# optocoupler-shield.net
KiCad netlist of a schematic drawn in EAGLE
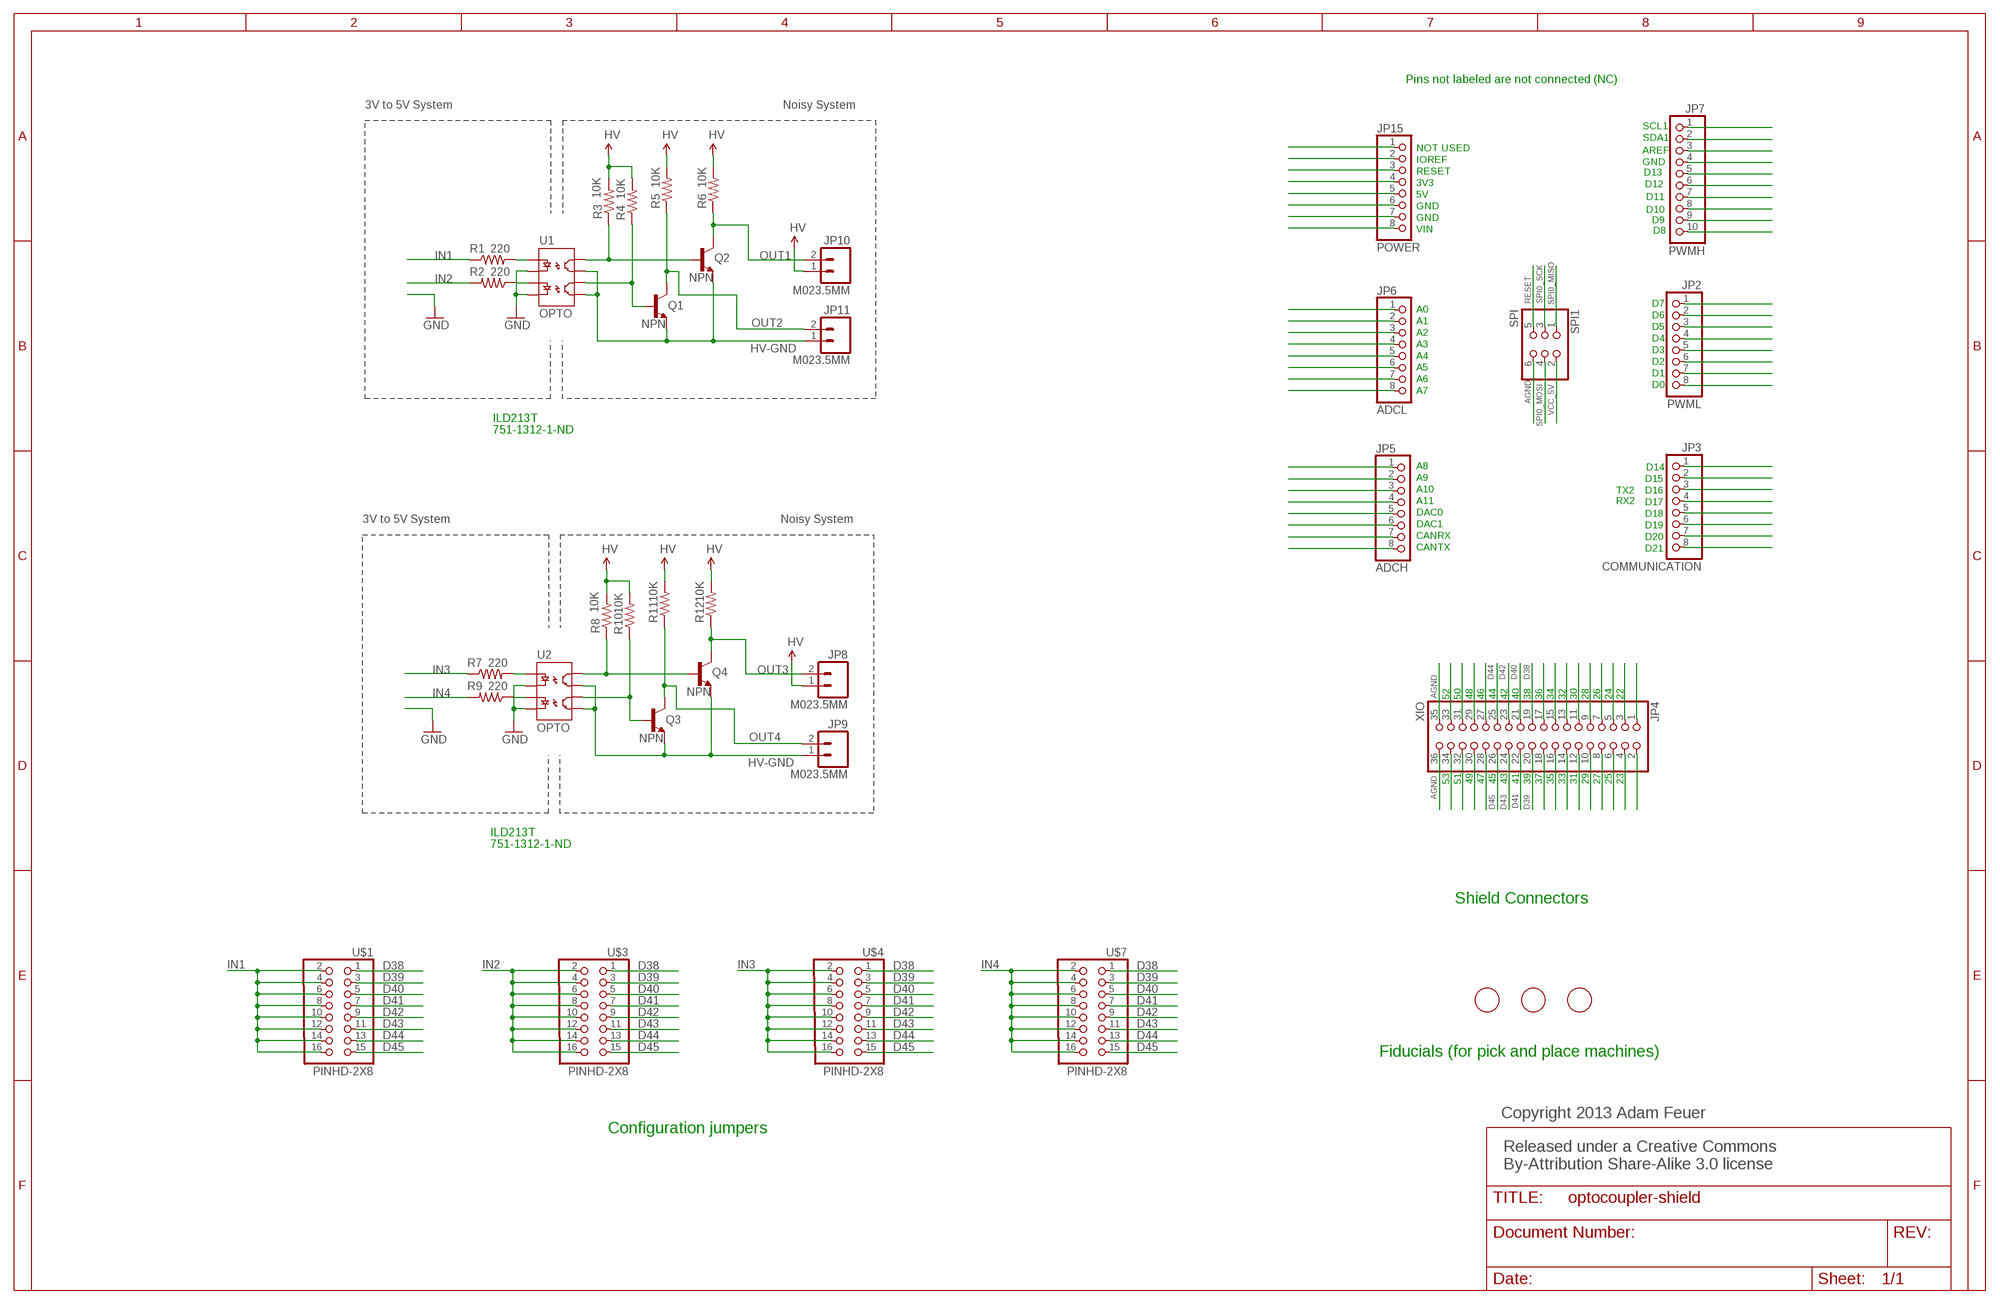
[diagram p0: schematic, sheet 1]

(export (version "E")
  (design (tool "Eeschema 10.0.6"))
  (components
    (comp (ref "JP2")
      (value "PWML")
      (footprint "eagle-import:1X08")
      (libsource (lib "eagle-import") (part "PINHD-1X8"))
    )
    (comp (ref "JP3")
      (value "COMMUNICATION")
      (footprint "eagle-import:1X08")
      (libsource (lib "eagle-import") (part "PINHD-1X8"))
    )
    (comp (ref "JP4")
      (value "XIO")
      (footprint "eagle-import:2X18")
      (libsource (lib "eagle-import") (part "PINHD-2X18"))
    )
    (comp (ref "JP5")
      (value "ADCH")
      (footprint "eagle-import:1X08")
      (libsource (lib "eagle-import") (part "PINHD-1X8"))
    )
    (comp (ref "JP6")
      (value "ADCL")
      (footprint "eagle-import:1X08")
      (libsource (lib "eagle-import") (part "PINHD-1X8"))
    )
    (comp (ref "JP7")
      (value "PWMH")
      (footprint "eagle-import:1X10")
      (libsource (lib "eagle-import") (part "PINHD-1X10"))
    )
    (comp (ref "JP8")
      (value "M023.5MM")
      (footprint "eagle-import:SCREWTERMINAL-3.5MM-2")
      (libsource (lib "eagle-import") (part "M023.5MM"))
    )
    (comp (ref "JP9")
      (value "M023.5MM")
      (footprint "eagle-import:SCREWTERMINAL-3.5MM-2")
      (libsource (lib "eagle-import") (part "M023.5MM"))
    )
    (comp (ref "JP10")
      (value "M023.5MM")
      (footprint "eagle-import:SCREWTERMINAL-3.5MM-2")
      (libsource (lib "eagle-import") (part "M023.5MM"))
    )
    (comp (ref "JP11")
      (value "M023.5MM")
      (footprint "eagle-import:SCREWTERMINAL-3.5MM-2")
      (libsource (lib "eagle-import") (part "M023.5MM"))
    )
    (comp (ref "JP15")
      (value "POWER")
      (footprint "eagle-import:1X08")
      (libsource (lib "eagle-import") (part "PINHD-1X8"))
    )
    (comp (ref "Q1")
      (value "NPN")
      (footprint "eagle-import:SOT23-3")
      (libsource (lib "eagle-import") (part "TRANSISTOR_NPNSOT23-3"))
    )
    (comp (ref "Q2")
      (value "NPN")
      (footprint "eagle-import:SOT23-3")
      (libsource (lib "eagle-import") (part "TRANSISTOR_NPNSOT23-3"))
    )
    (comp (ref "Q3")
      (value "NPN")
      (footprint "eagle-import:SOT23-3")
      (libsource (lib "eagle-import") (part "TRANSISTOR_NPNSOT23-3"))
    )
    (comp (ref "Q4")
      (value "NPN")
      (footprint "eagle-import:SOT23-3")
      (libsource (lib "eagle-import") (part "TRANSISTOR_NPNSOT23-3"))
    )
    (comp (ref "R1")
      (value "220")
      (footprint "eagle-import:C0402")
      (libsource (lib "eagle-import") (part "RESISTOR0402"))
    )
    (comp (ref "R2")
      (value "220")
      (footprint "eagle-import:C0402")
      (libsource (lib "eagle-import") (part "RESISTOR0402"))
    )
    (comp (ref "R3")
      (value "10K")
      (footprint "eagle-import:C0402")
      (libsource (lib "eagle-import") (part "RESISTOR0402"))
    )
    (comp (ref "R4")
      (value "10K")
      (footprint "eagle-import:C0402")
      (libsource (lib "eagle-import") (part "RESISTOR0402"))
    )
    (comp (ref "R5")
      (value "10K")
      (footprint "eagle-import:C0402")
      (libsource (lib "eagle-import") (part "RESISTOR0402"))
    )
    (comp (ref "R6")
      (value "10K")
      (footprint "eagle-import:C0402")
      (libsource (lib "eagle-import") (part "RESISTOR0402"))
    )
    (comp (ref "R7")
      (value "220")
      (footprint "eagle-import:C0402")
      (libsource (lib "eagle-import") (part "RESISTOR0402"))
    )
    (comp (ref "R8")
      (value "10K")
      (footprint "eagle-import:C0402")
      (libsource (lib "eagle-import") (part "RESISTOR0402"))
    )
    (comp (ref "R9")
      (value "220")
      (footprint "eagle-import:C0402")
      (libsource (lib "eagle-import") (part "RESISTOR0402"))
    )
    (comp (ref "R10")
      (value "10K")
      (footprint "eagle-import:C0402")
      (libsource (lib "eagle-import") (part "RESISTOR0402"))
    )
    (comp (ref "R11")
      (value "10K")
      (footprint "eagle-import:C0402")
      (libsource (lib "eagle-import") (part "RESISTOR0402"))
    )
    (comp (ref "R12")
      (value "10K")
      (footprint "eagle-import:C0402")
      (libsource (lib "eagle-import") (part "RESISTOR0402"))
    )
    (comp (ref "SPI1")
      (value "SPI")
      (footprint "eagle-import:2X03")
      (libsource (lib "eagle-import") (part "PINHD-2X3"))
    )
    (comp (ref "U$1")
      (value "PINHD-2X8")
      (footprint "eagle-import:2X08")
      (libsource (lib "eagle-import") (part "PINHD-2X8"))
    )
    (comp (ref "U$2")
      (value "FIDUCIAL")
      (footprint "eagle-import:FIDUCIAL_1MM")
      (libsource (lib "eagle-import") (part "FIDUCIAL"))
    )
    (comp (ref "U$3")
      (value "PINHD-2X8")
      (footprint "eagle-import:2X08")
      (libsource (lib "eagle-import") (part "PINHD-2X8"))
    )
    (comp (ref "U$4")
      (value "PINHD-2X8")
      (footprint "eagle-import:2X08")
      (libsource (lib "eagle-import") (part "PINHD-2X8"))
    )
    (comp (ref "U$5")
      (value "FIDUCIAL")
      (footprint "eagle-import:FIDUCIAL_1MM")
      (libsource (lib "eagle-import") (part "FIDUCIAL"))
    )
    (comp (ref "U$6")
      (value "FIDUCIAL")
      (footprint "eagle-import:FIDUCIAL_1MM")
      (libsource (lib "eagle-import") (part "FIDUCIAL"))
    )
    (comp (ref "U$7")
      (value "PINHD-2X8")
      (footprint "eagle-import:2X08")
      (libsource (lib "eagle-import") (part "PINHD-2X8"))
    )
    (comp (ref "U1")
      (value "OPTO")
      (footprint "eagle-import:SO08-2")
      (libsource (lib "eagle-import") (part "OPTOISOLATOR-2SOIC8"))
    )
    (comp (ref "U2")
      (value "OPTO")
      (footprint "eagle-import:SO08-2")
      (libsource (lib "eagle-import") (part "OPTOISOLATOR-2SOIC8"))
    )
  )
  (nets
    (net (code "1") (name "/AGND") (class "Default")
      (node (ref "JP4") (pin "35") (pinfunction "35_35") (pintype "passive"))
      (node (ref "JP4") (pin "36") (pinfunction "36_36") (pintype "passive"))
      (node (ref "SPI1") (pin "6") (pinfunction "6_6") (pintype "passive"))
    )
    (net (code "2") (name "/D38") (class "Default")
      (node (ref "JP4") (pin "19") (pinfunction "19_19") (pintype "passive"))
      (node (ref "U$1") (pin "1") (pinfunction "1_1") (pintype "passive"))
      (node (ref "U$3") (pin "1") (pinfunction "1_1") (pintype "passive"))
      (node (ref "U$4") (pin "1") (pinfunction "1_1") (pintype "passive"))
      (node (ref "U$7") (pin "1") (pinfunction "1_1") (pintype "passive"))
    )
    (net (code "3") (name "/D39") (class "Default")
      (node (ref "JP4") (pin "20") (pinfunction "20_20") (pintype "passive"))
      (node (ref "U$1") (pin "3") (pinfunction "3_3") (pintype "passive"))
      (node (ref "U$3") (pin "3") (pinfunction "3_3") (pintype "passive"))
      (node (ref "U$4") (pin "3") (pinfunction "3_3") (pintype "passive"))
      (node (ref "U$7") (pin "3") (pinfunction "3_3") (pintype "passive"))
    )
    (net (code "4") (name "/D40") (class "Default")
      (node (ref "JP4") (pin "21") (pinfunction "21_21") (pintype "passive"))
      (node (ref "U$1") (pin "5") (pinfunction "5_5") (pintype "passive"))
      (node (ref "U$3") (pin "5") (pinfunction "5_5") (pintype "passive"))
      (node (ref "U$4") (pin "5") (pinfunction "5_5") (pintype "passive"))
      (node (ref "U$7") (pin "5") (pinfunction "5_5") (pintype "passive"))
    )
    (net (code "5") (name "/D41") (class "Default")
      (node (ref "JP4") (pin "22") (pinfunction "22_22") (pintype "passive"))
      (node (ref "U$1") (pin "7") (pinfunction "7_7") (pintype "passive"))
      (node (ref "U$3") (pin "7") (pinfunction "7_7") (pintype "passive"))
      (node (ref "U$4") (pin "7") (pinfunction "7_7") (pintype "passive"))
      (node (ref "U$7") (pin "7") (pinfunction "7_7") (pintype "passive"))
    )
    (net (code "6") (name "/D42") (class "Default")
      (node (ref "JP4") (pin "23") (pinfunction "23_23") (pintype "passive"))
      (node (ref "U$1") (pin "9") (pinfunction "9_9") (pintype "passive"))
      (node (ref "U$3") (pin "9") (pinfunction "9_9") (pintype "passive"))
      (node (ref "U$4") (pin "9") (pinfunction "9_9") (pintype "passive"))
      (node (ref "U$7") (pin "9") (pinfunction "9_9") (pintype "passive"))
    )
    (net (code "7") (name "/D43") (class "Default")
      (node (ref "JP4") (pin "24") (pinfunction "24_24") (pintype "passive"))
      (node (ref "U$1") (pin "11") (pinfunction "11_11") (pintype "passive"))
      (node (ref "U$3") (pin "11") (pinfunction "11_11") (pintype "passive"))
      (node (ref "U$4") (pin "11") (pinfunction "11_11") (pintype "passive"))
      (node (ref "U$7") (pin "11") (pinfunction "11_11") (pintype "passive"))
    )
    (net (code "8") (name "/D44") (class "Default")
      (node (ref "JP4") (pin "25") (pinfunction "25_25") (pintype "passive"))
      (node (ref "U$1") (pin "13") (pinfunction "13_13") (pintype "passive"))
      (node (ref "U$3") (pin "13") (pinfunction "13_13") (pintype "passive"))
      (node (ref "U$4") (pin "13") (pinfunction "13_13") (pintype "passive"))
      (node (ref "U$7") (pin "13") (pinfunction "13_13") (pintype "passive"))
    )
    (net (code "9") (name "/D45") (class "Default")
      (node (ref "JP4") (pin "26") (pinfunction "26_26") (pintype "passive"))
      (node (ref "U$1") (pin "15") (pinfunction "15_15") (pintype "passive"))
      (node (ref "U$3") (pin "15") (pinfunction "15_15") (pintype "passive"))
      (node (ref "U$4") (pin "15") (pinfunction "15_15") (pintype "passive"))
      (node (ref "U$7") (pin "15") (pinfunction "15_15") (pintype "passive"))
    )
    (net (code "10") (name "/HV-GND") (class "Default")
      (node (ref "JP11") (pin "1") (pinfunction "1_1") (pintype "passive"))
      (node (ref "JP9") (pin "1") (pinfunction "1_1") (pintype "passive"))
      (node (ref "Q1") (pin "2") (pinfunction "E_2") (pintype "passive"))
      (node (ref "Q2") (pin "2") (pinfunction "E_2") (pintype "passive"))
      (node (ref "Q3") (pin "2") (pinfunction "E_2") (pintype "passive"))
      (node (ref "Q4") (pin "2") (pinfunction "E_2") (pintype "passive"))
      (node (ref "U1") (pin "5") (pinfunction "EM2_5") (pintype "bidirectional"))
      (node (ref "U1") (pin "7") (pinfunction "EM1_7") (pintype "bidirectional"))
      (node (ref "U2") (pin "5") (pinfunction "EM2_5") (pintype "bidirectional"))
      (node (ref "U2") (pin "7") (pinfunction "EM1_7") (pintype "bidirectional"))
    )
    (net (code "11") (name "/IN1") (class "Default")
      (node (ref "R1") (pin "1") (pinfunction "1_1") (pintype "passive"))
      (node (ref "U$1") (pin "10") (pinfunction "10_10") (pintype "passive"))
      (node (ref "U$1") (pin "12") (pinfunction "12_12") (pintype "passive"))
      (node (ref "U$1") (pin "14") (pinfunction "14_14") (pintype "passive"))
      (node (ref "U$1") (pin "16") (pinfunction "16_16") (pintype "passive"))
      (node (ref "U$1") (pin "2") (pinfunction "2_2") (pintype "passive"))
      (node (ref "U$1") (pin "4") (pinfunction "4_4") (pintype "passive"))
      (node (ref "U$1") (pin "6") (pinfunction "6_6") (pintype "passive"))
      (node (ref "U$1") (pin "8") (pinfunction "8_8") (pintype "passive"))
    )
    (net (code "12") (name "/IN2") (class "Default")
      (node (ref "R2") (pin "2") (pinfunction "2_2") (pintype "passive"))
      (node (ref "U$3") (pin "10") (pinfunction "10_10") (pintype "passive"))
      (node (ref "U$3") (pin "12") (pinfunction "12_12") (pintype "passive"))
      (node (ref "U$3") (pin "14") (pinfunction "14_14") (pintype "passive"))
      (node (ref "U$3") (pin "16") (pinfunction "16_16") (pintype "passive"))
      (node (ref "U$3") (pin "2") (pinfunction "2_2") (pintype "passive"))
      (node (ref "U$3") (pin "4") (pinfunction "4_4") (pintype "passive"))
      (node (ref "U$3") (pin "6") (pinfunction "6_6") (pintype "passive"))
      (node (ref "U$3") (pin "8") (pinfunction "8_8") (pintype "passive"))
    )
    (net (code "13") (name "/IN3") (class "Default")
      (node (ref "R7") (pin "1") (pinfunction "1_1") (pintype "passive"))
      (node (ref "U$4") (pin "10") (pinfunction "10_10") (pintype "passive"))
      (node (ref "U$4") (pin "12") (pinfunction "12_12") (pintype "passive"))
      (node (ref "U$4") (pin "14") (pinfunction "14_14") (pintype "passive"))
      (node (ref "U$4") (pin "16") (pinfunction "16_16") (pintype "passive"))
      (node (ref "U$4") (pin "2") (pinfunction "2_2") (pintype "passive"))
      (node (ref "U$4") (pin "4") (pinfunction "4_4") (pintype "passive"))
      (node (ref "U$4") (pin "6") (pinfunction "6_6") (pintype "passive"))
      (node (ref "U$4") (pin "8") (pinfunction "8_8") (pintype "passive"))
    )
    (net (code "14") (name "/IN4") (class "Default")
      (node (ref "R9") (pin "2") (pinfunction "2_2") (pintype "passive"))
      (node (ref "U$7") (pin "10") (pinfunction "10_10") (pintype "passive"))
      (node (ref "U$7") (pin "12") (pinfunction "12_12") (pintype "passive"))
      (node (ref "U$7") (pin "14") (pinfunction "14_14") (pintype "passive"))
      (node (ref "U$7") (pin "16") (pinfunction "16_16") (pintype "passive"))
      (node (ref "U$7") (pin "2") (pinfunction "2_2") (pintype "passive"))
      (node (ref "U$7") (pin "4") (pinfunction "4_4") (pintype "passive"))
      (node (ref "U$7") (pin "6") (pinfunction "6_6") (pintype "passive"))
      (node (ref "U$7") (pin "8") (pinfunction "8_8") (pintype "passive"))
    )
    (net (code "15") (name "/OUT1") (class "Default")
      (node (ref "JP10") (pin "2") (pinfunction "2_2") (pintype "passive"))
      (node (ref "Q2") (pin "3") (pinfunction "C_3") (pintype "passive"))
      (node (ref "R6") (pin "1") (pinfunction "1_1") (pintype "passive"))
    )
    (net (code "16") (name "/OUT2") (class "Default")
      (node (ref "JP11") (pin "2") (pinfunction "2_2") (pintype "passive"))
      (node (ref "Q1") (pin "3") (pinfunction "C_3") (pintype "passive"))
      (node (ref "R5") (pin "1") (pinfunction "1_1") (pintype "passive"))
    )
    (net (code "17") (name "/OUT3") (class "Default")
      (node (ref "JP8") (pin "2") (pinfunction "2_2") (pintype "passive"))
      (node (ref "Q4") (pin "3") (pinfunction "C_3") (pintype "passive"))
      (node (ref "R12") (pin "1") (pinfunction "1_1") (pintype "passive"))
    )
    (net (code "18") (name "/OUT4") (class "Default")
      (node (ref "JP9") (pin "2") (pinfunction "2_2") (pintype "passive"))
      (node (ref "Q3") (pin "3") (pinfunction "C_3") (pintype "passive"))
      (node (ref "R11") (pin "1") (pinfunction "1_1") (pintype "passive"))
    )
    (net (code "19") (name "/RESET") (class "Default")
      (node (ref "SPI1") (pin "5") (pinfunction "5_5") (pintype "passive"))
    )
    (net (code "20") (name "/SPI0_MISO") (class "Default")
      (node (ref "SPI1") (pin "1") (pinfunction "1_1") (pintype "passive"))
    )
    (net (code "21") (name "/SPI0_MOSI") (class "Default")
      (node (ref "SPI1") (pin "4") (pinfunction "4_4") (pintype "passive"))
    )
    (net (code "22") (name "/SPI0_SCK") (class "Default")
      (node (ref "SPI1") (pin "3") (pinfunction "3_3") (pintype "passive"))
    )
    (net (code "23") (name "/VCC_5V") (class "Default")
      (node (ref "SPI1") (pin "2") (pinfunction "2_2") (pintype "passive"))
    )
    (net (code "24") (name "GND") (class "Default")
      (node (ref "U1") (pin "2") (pinfunction "C1_2") (pintype "bidirectional"))
      (node (ref "U1") (pin "4") (pinfunction "C2_4") (pintype "bidirectional"))
      (node (ref "U2") (pin "2") (pinfunction "C1_2") (pintype "bidirectional"))
      (node (ref "U2") (pin "4") (pinfunction "C2_4") (pintype "bidirectional"))
    )
    (net (code "25") (name "HV") (class "Default")
      (node (ref "JP10") (pin "1") (pinfunction "1_1") (pintype "passive"))
      (node (ref "JP8") (pin "1") (pinfunction "1_1") (pintype "passive"))
      (node (ref "R10") (pin "2") (pinfunction "2_2") (pintype "passive"))
      (node (ref "R11") (pin "2") (pinfunction "2_2") (pintype "passive"))
      (node (ref "R12") (pin "2") (pinfunction "2_2") (pintype "passive"))
      (node (ref "R3") (pin "2") (pinfunction "2_2") (pintype "passive"))
      (node (ref "R4") (pin "2") (pinfunction "2_2") (pintype "passive"))
      (node (ref "R5") (pin "2") (pinfunction "2_2") (pintype "passive"))
      (node (ref "R6") (pin "2") (pinfunction "2_2") (pintype "passive"))
      (node (ref "R8") (pin "2") (pinfunction "2_2") (pintype "passive"))
    )
    (net (code "26") (name "Net-(Q1-B)") (class "Default")
      (node (ref "Q1") (pin "1") (pinfunction "B_1") (pintype "passive"))
      (node (ref "R4") (pin "1") (pinfunction "1_1") (pintype "passive"))
      (node (ref "U1") (pin "6") (pinfunction "CL2_6") (pintype "bidirectional"))
    )
    (net (code "27") (name "Net-(Q2-B)") (class "Default")
      (node (ref "Q2") (pin "1") (pinfunction "B_1") (pintype "passive"))
      (node (ref "R3") (pin "1") (pinfunction "1_1") (pintype "passive"))
      (node (ref "U1") (pin "8") (pinfunction "CL1_8") (pintype "bidirectional"))
    )
    (net (code "28") (name "Net-(Q3-B)") (class "Default")
      (node (ref "Q3") (pin "1") (pinfunction "B_1") (pintype "passive"))
      (node (ref "R10") (pin "1") (pinfunction "1_1") (pintype "passive"))
      (node (ref "U2") (pin "6") (pinfunction "CL2_6") (pintype "bidirectional"))
    )
    (net (code "29") (name "Net-(Q4-B)") (class "Default")
      (node (ref "Q4") (pin "1") (pinfunction "B_1") (pintype "passive"))
      (node (ref "R8") (pin "1") (pinfunction "1_1") (pintype "passive"))
      (node (ref "U2") (pin "8") (pinfunction "CL1_8") (pintype "bidirectional"))
    )
    (net (code "30") (name "Net-(U1-A1)") (class "Default")
      (node (ref "R1") (pin "2") (pinfunction "2_2") (pintype "passive"))
      (node (ref "U1") (pin "1") (pinfunction "A1_1") (pintype "bidirectional"))
    )
    (net (code "31") (name "Net-(U1-A2)") (class "Default")
      (node (ref "R2") (pin "1") (pinfunction "1_1") (pintype "passive"))
      (node (ref "U1") (pin "3") (pinfunction "A2_3") (pintype "bidirectional"))
    )
    (net (code "32") (name "Net-(U2-A1)") (class "Default")
      (node (ref "R7") (pin "2") (pinfunction "2_2") (pintype "passive"))
      (node (ref "U2") (pin "1") (pinfunction "A1_1") (pintype "bidirectional"))
    )
    (net (code "33") (name "Net-(U2-A2)") (class "Default")
      (node (ref "R9") (pin "1") (pinfunction "1_1") (pintype "passive"))
      (node (ref "U2") (pin "3") (pinfunction "A2_3") (pintype "bidirectional"))
    )
    (net (code "34") (name "unconnected-(JP2-Pad1)") (class "Default")
      (node (ref "JP2") (pin "1") (pinfunction "1_1") (pintype "passive"))
    )
    (net (code "35") (name "unconnected-(JP2-Pad2)") (class "Default")
      (node (ref "JP2") (pin "2") (pinfunction "2_2") (pintype "passive"))
    )
    (net (code "36") (name "unconnected-(JP2-Pad3)") (class "Default")
      (node (ref "JP2") (pin "3") (pinfunction "3_3") (pintype "passive"))
    )
    (net (code "37") (name "unconnected-(JP2-Pad4)") (class "Default")
      (node (ref "JP2") (pin "4") (pinfunction "4_4") (pintype "passive"))
    )
    (net (code "38") (name "unconnected-(JP2-Pad5)") (class "Default")
      (node (ref "JP2") (pin "5") (pinfunction "5_5") (pintype "passive"))
    )
    (net (code "39") (name "unconnected-(JP2-Pad6)") (class "Default")
      (node (ref "JP2") (pin "6") (pinfunction "6_6") (pintype "passive"))
    )
    (net (code "40") (name "unconnected-(JP2-Pad7)") (class "Default")
      (node (ref "JP2") (pin "7") (pinfunction "7_7") (pintype "passive"))
    )
    (net (code "41") (name "unconnected-(JP2-Pad8)") (class "Default")
      (node (ref "JP2") (pin "8") (pinfunction "8_8") (pintype "passive"))
    )
    (net (code "42") (name "unconnected-(JP3-Pad1)") (class "Default")
      (node (ref "JP3") (pin "1") (pinfunction "1_1") (pintype "passive"))
    )
    (net (code "43") (name "unconnected-(JP3-Pad2)") (class "Default")
      (node (ref "JP3") (pin "2") (pinfunction "2_2") (pintype "passive"))
    )
    (net (code "44") (name "unconnected-(JP3-Pad3)") (class "Default")
      (node (ref "JP3") (pin "3") (pinfunction "3_3") (pintype "passive"))
    )
    (net (code "45") (name "unconnected-(JP3-Pad4)") (class "Default")
      (node (ref "JP3") (pin "4") (pinfunction "4_4") (pintype "passive"))
    )
    (net (code "46") (name "unconnected-(JP3-Pad5)") (class "Default")
      (node (ref "JP3") (pin "5") (pinfunction "5_5") (pintype "passive"))
    )
    (net (code "47") (name "unconnected-(JP3-Pad6)") (class "Default")
      (node (ref "JP3") (pin "6") (pinfunction "6_6") (pintype "passive"))
    )
    (net (code "48") (name "unconnected-(JP3-Pad7)") (class "Default")
      (node (ref "JP3") (pin "7") (pinfunction "7_7") (pintype "passive"))
    )
    (net (code "49") (name "unconnected-(JP3-Pad8)") (class "Default")
      (node (ref "JP3") (pin "8") (pinfunction "8_8") (pintype "passive"))
    )
    (net (code "50") (name "unconnected-(JP4-Pad1)") (class "Default")
      (node (ref "JP4") (pin "1") (pinfunction "1_1") (pintype "passive"))
    )
    (net (code "51") (name "unconnected-(JP4-Pad2)") (class "Default")
      (node (ref "JP4") (pin "2") (pinfunction "2_2") (pintype "passive"))
    )
    (net (code "52") (name "unconnected-(JP4-Pad3)") (class "Default")
      (node (ref "JP4") (pin "3") (pinfunction "3_3") (pintype "passive"))
    )
    (net (code "53") (name "unconnected-(JP4-Pad4)") (class "Default")
      (node (ref "JP4") (pin "4") (pinfunction "4_4") (pintype "passive"))
    )
    (net (code "54") (name "unconnected-(JP4-Pad5)") (class "Default")
      (node (ref "JP4") (pin "5") (pinfunction "5_5") (pintype "passive"))
    )
    (net (code "55") (name "unconnected-(JP4-Pad6)") (class "Default")
      (node (ref "JP4") (pin "6") (pinfunction "6_6") (pintype "passive"))
    )
    (net (code "56") (name "unconnected-(JP4-Pad7)") (class "Default")
      (node (ref "JP4") (pin "7") (pinfunction "7_7") (pintype "passive"))
    )
    (net (code "57") (name "unconnected-(JP4-Pad8)") (class "Default")
      (node (ref "JP4") (pin "8") (pinfunction "8_8") (pintype "passive"))
    )
    (net (code "58") (name "unconnected-(JP4-Pad9)") (class "Default")
      (node (ref "JP4") (pin "9") (pinfunction "9_9") (pintype "passive"))
    )
    (net (code "59") (name "unconnected-(JP4-Pad10)") (class "Default")
      (node (ref "JP4") (pin "10") (pinfunction "10_10") (pintype "passive"))
    )
    (net (code "60") (name "unconnected-(JP4-Pad11)") (class "Default")
      (node (ref "JP4") (pin "11") (pinfunction "11_11") (pintype "passive"))
    )
    (net (code "61") (name "unconnected-(JP4-Pad12)") (class "Default")
      (node (ref "JP4") (pin "12") (pinfunction "12_12") (pintype "passive"))
    )
    (net (code "62") (name "unconnected-(JP4-Pad13)") (class "Default")
      (node (ref "JP4") (pin "13") (pinfunction "13_13") (pintype "passive"))
    )
    (net (code "63") (name "unconnected-(JP4-Pad14)") (class "Default")
      (node (ref "JP4") (pin "14") (pinfunction "14_14") (pintype "passive"))
    )
    (net (code "64") (name "unconnected-(JP4-Pad15)") (class "Default")
      (node (ref "JP4") (pin "15") (pinfunction "15_15") (pintype "passive"))
    )
    (net (code "65") (name "unconnected-(JP4-Pad16)") (class "Default")
      (node (ref "JP4") (pin "16") (pinfunction "16_16") (pintype "passive"))
    )
    (net (code "66") (name "unconnected-(JP4-Pad17)") (class "Default")
      (node (ref "JP4") (pin "17") (pinfunction "17_17") (pintype "passive"))
    )
    (net (code "67") (name "unconnected-(JP4-Pad18)") (class "Default")
      (node (ref "JP4") (pin "18") (pinfunction "18_18") (pintype "passive"))
    )
    (net (code "68") (name "unconnected-(JP4-Pad27)") (class "Default")
      (node (ref "JP4") (pin "27") (pinfunction "27_27") (pintype "passive"))
    )
    (net (code "69") (name "unconnected-(JP4-Pad28)") (class "Default")
      (node (ref "JP4") (pin "28") (pinfunction "28_28") (pintype "passive"))
    )
    (net (code "70") (name "unconnected-(JP4-Pad29)") (class "Default")
      (node (ref "JP4") (pin "29") (pinfunction "29_29") (pintype "passive"))
    )
    (net (code "71") (name "unconnected-(JP4-Pad30)") (class "Default")
      (node (ref "JP4") (pin "30") (pinfunction "30_30") (pintype "passive"))
    )
    (net (code "72") (name "unconnected-(JP4-Pad31)") (class "Default")
      (node (ref "JP4") (pin "31") (pinfunction "31_31") (pintype "passive"))
    )
    (net (code "73") (name "unconnected-(JP4-Pad32)") (class "Default")
      (node (ref "JP4") (pin "32") (pinfunction "32_32") (pintype "passive"))
    )
    (net (code "74") (name "unconnected-(JP4-Pad33)") (class "Default")
      (node (ref "JP4") (pin "33") (pinfunction "33_33") (pintype "passive"))
    )
    (net (code "75") (name "unconnected-(JP4-Pad34)") (class "Default")
      (node (ref "JP4") (pin "34") (pinfunction "34_34") (pintype "passive"))
    )
    (net (code "76") (name "unconnected-(JP5-Pad1)") (class "Default")
      (node (ref "JP5") (pin "1") (pinfunction "1_1") (pintype "passive"))
    )
    (net (code "77") (name "unconnected-(JP5-Pad2)") (class "Default")
      (node (ref "JP5") (pin "2") (pinfunction "2_2") (pintype "passive"))
    )
    (net (code "78") (name "unconnected-(JP5-Pad3)") (class "Default")
      (node (ref "JP5") (pin "3") (pinfunction "3_3") (pintype "passive"))
    )
    (net (code "79") (name "unconnected-(JP5-Pad4)") (class "Default")
      (node (ref "JP5") (pin "4") (pinfunction "4_4") (pintype "passive"))
    )
    (net (code "80") (name "unconnected-(JP5-Pad5)") (class "Default")
      (node (ref "JP5") (pin "5") (pinfunction "5_5") (pintype "passive"))
    )
    (net (code "81") (name "unconnected-(JP5-Pad6)") (class "Default")
      (node (ref "JP5") (pin "6") (pinfunction "6_6") (pintype "passive"))
    )
    (net (code "82") (name "unconnected-(JP5-Pad7)") (class "Default")
      (node (ref "JP5") (pin "7") (pinfunction "7_7") (pintype "passive"))
    )
    (net (code "83") (name "unconnected-(JP5-Pad8)") (class "Default")
      (node (ref "JP5") (pin "8") (pinfunction "8_8") (pintype "passive"))
    )
    (net (code "84") (name "unconnected-(JP6-Pad1)") (class "Default")
      (node (ref "JP6") (pin "1") (pinfunction "1_1") (pintype "passive"))
    )
    (net (code "85") (name "unconnected-(JP6-Pad2)") (class "Default")
      (node (ref "JP6") (pin "2") (pinfunction "2_2") (pintype "passive"))
    )
    (net (code "86") (name "unconnected-(JP6-Pad3)") (class "Default")
      (node (ref "JP6") (pin "3") (pinfunction "3_3") (pintype "passive"))
    )
    (net (code "87") (name "unconnected-(JP6-Pad4)") (class "Default")
      (node (ref "JP6") (pin "4") (pinfunction "4_4") (pintype "passive"))
    )
    (net (code "88") (name "unconnected-(JP6-Pad5)") (class "Default")
      (node (ref "JP6") (pin "5") (pinfunction "5_5") (pintype "passive"))
    )
    (net (code "89") (name "unconnected-(JP6-Pad6)") (class "Default")
      (node (ref "JP6") (pin "6") (pinfunction "6_6") (pintype "passive"))
    )
    (net (code "90") (name "unconnected-(JP6-Pad7)") (class "Default")
      (node (ref "JP6") (pin "7") (pinfunction "7_7") (pintype "passive"))
    )
    (net (code "91") (name "unconnected-(JP6-Pad8)") (class "Default")
      (node (ref "JP6") (pin "8") (pinfunction "8_8") (pintype "passive"))
    )
    (net (code "92") (name "unconnected-(JP7-Pad1)") (class "Default")
      (node (ref "JP7") (pin "1") (pinfunction "1_1") (pintype "passive"))
    )
    (net (code "93") (name "unconnected-(JP7-Pad2)") (class "Default")
      (node (ref "JP7") (pin "2") (pinfunction "2_2") (pintype "passive"))
    )
    (net (code "94") (name "unconnected-(JP7-Pad3)") (class "Default")
      (node (ref "JP7") (pin "3") (pinfunction "3_3") (pintype "passive"))
    )
    (net (code "95") (name "unconnected-(JP7-Pad4)") (class "Default")
      (node (ref "JP7") (pin "4") (pinfunction "4_4") (pintype "passive"))
    )
    (net (code "96") (name "unconnected-(JP7-Pad5)") (class "Default")
      (node (ref "JP7") (pin "5") (pinfunction "5_5") (pintype "passive"))
    )
    (net (code "97") (name "unconnected-(JP7-Pad6)") (class "Default")
      (node (ref "JP7") (pin "6") (pinfunction "6_6") (pintype "passive"))
    )
    (net (code "98") (name "unconnected-(JP7-Pad7)") (class "Default")
      (node (ref "JP7") (pin "7") (pinfunction "7_7") (pintype "passive"))
    )
    (net (code "99") (name "unconnected-(JP7-Pad8)") (class "Default")
      (node (ref "JP7") (pin "8") (pinfunction "8_8") (pintype "passive"))
    )
    (net (code "100") (name "unconnected-(JP7-Pad9)") (class "Default")
      (node (ref "JP7") (pin "9") (pinfunction "9_9") (pintype "passive"))
    )
    (net (code "101") (name "unconnected-(JP7-Pad10)") (class "Default")
      (node (ref "JP7") (pin "10") (pinfunction "10_10") (pintype "passive"))
    )
    (net (code "102") (name "unconnected-(JP15-Pad1)") (class "Default")
      (node (ref "JP15") (pin "1") (pinfunction "1_1") (pintype "passive"))
    )
    (net (code "103") (name "unconnected-(JP15-Pad2)") (class "Default")
      (node (ref "JP15") (pin "2") (pinfunction "2_2") (pintype "passive"))
    )
    (net (code "104") (name "unconnected-(JP15-Pad3)") (class "Default")
      (node (ref "JP15") (pin "3") (pinfunction "3_3") (pintype "passive"))
    )
    (net (code "105") (name "unconnected-(JP15-Pad4)") (class "Default")
      (node (ref "JP15") (pin "4") (pinfunction "4_4") (pintype "passive"))
    )
    (net (code "106") (name "unconnected-(JP15-Pad5)") (class "Default")
      (node (ref "JP15") (pin "5") (pinfunction "5_5") (pintype "passive"))
    )
    (net (code "107") (name "unconnected-(JP15-Pad6)") (class "Default")
      (node (ref "JP15") (pin "6") (pinfunction "6_6") (pintype "passive"))
    )
    (net (code "108") (name "unconnected-(JP15-Pad7)") (class "Default")
      (node (ref "JP15") (pin "7") (pinfunction "7_7") (pintype "passive"))
    )
    (net (code "109") (name "unconnected-(JP15-Pad8)") (class "Default")
      (node (ref "JP15") (pin "8") (pinfunction "8_8") (pintype "passive"))
    )
  )
)
